# Encodeurs_Schematic.net
KiCad netlist of a schematic drawn in Altium Designer
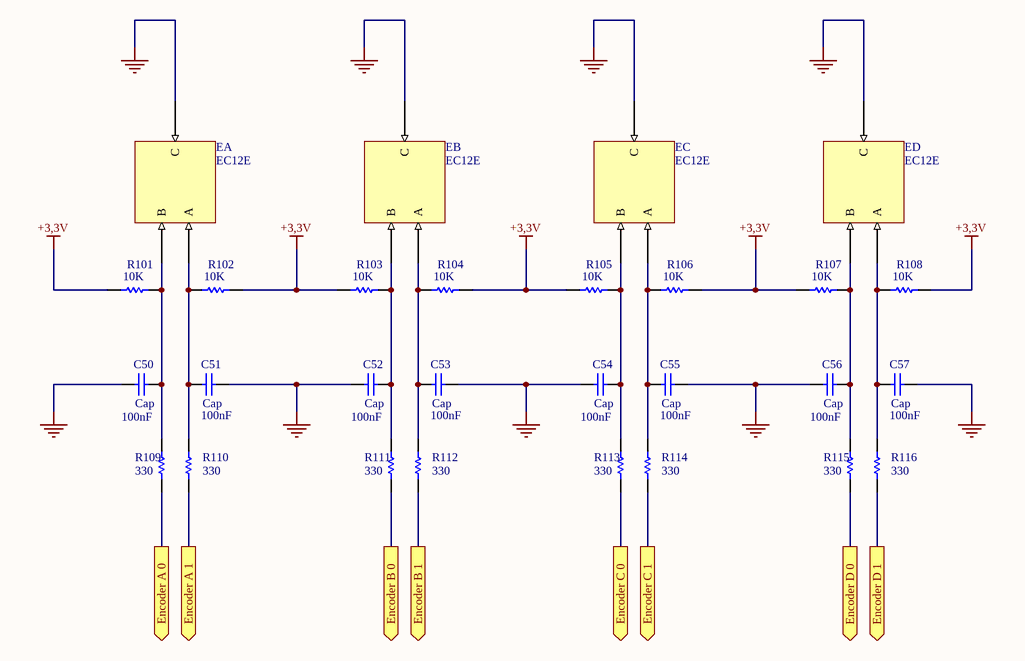
[diagram p0: Encodeurs.Schematic.SchDoc]

(export (version "E")
  (design (tool "Eeschema 10.0.6"))
  (components
    (comp (ref "C50")
      (value "Cap")
      (footprint "CAPC1608N - cap")
      (description "Capacitor")
      (fields (field (name "ALTIUM_VALUE") "100nF") (field (name "PUBLISHER") "Altium Limited"))
      (libsource (lib "Miscellaneous Devices") (part "Cap"))
    )
    (comp (ref "C51")
      (value "Cap")
      (footprint "CAPC1608N - cap")
      (description "Capacitor")
      (fields (field (name "ALTIUM_VALUE") "100nF") (field (name "PUBLISHER") "Altium Limited"))
      (libsource (lib "Miscellaneous Devices") (part "Cap"))
    )
    (comp (ref "C52")
      (value "Cap")
      (footprint "CAPC1608N - cap")
      (description "Capacitor")
      (fields (field (name "ALTIUM_VALUE") "100nF") (field (name "PUBLISHER") "Altium Limited"))
      (libsource (lib "Miscellaneous Devices") (part "Cap"))
    )
    (comp (ref "C53")
      (value "Cap")
      (footprint "CAPC1608N - cap")
      (description "Capacitor")
      (fields (field (name "ALTIUM_VALUE") "100nF") (field (name "PUBLISHER") "Altium Limited"))
      (libsource (lib "Miscellaneous Devices") (part "Cap"))
    )
    (comp (ref "C54")
      (value "Cap")
      (footprint "CAPC1608N - cap")
      (description "Capacitor")
      (fields (field (name "ALTIUM_VALUE") "100nF") (field (name "PUBLISHER") "Altium Limited"))
      (libsource (lib "Miscellaneous Devices") (part "Cap"))
    )
    (comp (ref "C55")
      (value "Cap")
      (footprint "CAPC1608N - cap")
      (description "Capacitor")
      (fields (field (name "ALTIUM_VALUE") "100nF") (field (name "PUBLISHER") "Altium Limited"))
      (libsource (lib "Miscellaneous Devices") (part "Cap"))
    )
    (comp (ref "C56")
      (value "Cap")
      (footprint "CAPC1608N - cap")
      (description "Capacitor")
      (fields (field (name "ALTIUM_VALUE") "100nF") (field (name "PUBLISHER") "Altium Limited"))
      (libsource (lib "Miscellaneous Devices") (part "Cap"))
    )
    (comp (ref "C57")
      (value "Cap")
      (footprint "CAPC1608N - cap")
      (description "Capacitor")
      (fields (field (name "ALTIUM_VALUE") "100nF") (field (name "PUBLISHER") "Altium Limited"))
      (libsource (lib "Miscellaneous Devices") (part "Cap"))
    )
    (comp (ref "EA")
      (value "EC12E")
      (footprint "EC12E")
      (libsource (lib "SynthyTwo.Components") (part "EC12E"))
    )
    (comp (ref "EB")
      (value "EC12E")
      (footprint "EC12E")
      (libsource (lib "SynthyTwo.Components") (part "EC12E"))
    )
    (comp (ref "EC")
      (value "EC12E")
      (footprint "EC12E")
      (libsource (lib "SynthyTwo.Components") (part "EC12E"))
    )
    (comp (ref "ED")
      (value "EC12E")
      (footprint "EC12E")
      (libsource (lib "SynthyTwo.Components") (part "EC12E"))
    )
    (comp (ref "R101")
      (value "10K")
      (footprint "CAPC1608N")
      (description "Resistor")
      (fields (field (name "PUBLISHER") "Altium Limited"))
      (libsource (lib "Miscellaneous Devices") (part "Res1"))
    )
    (comp (ref "R102")
      (value "10K")
      (footprint "CAPC1608N")
      (description "Resistor")
      (fields (field (name "PUBLISHER") "Altium Limited"))
      (libsource (lib "Miscellaneous Devices") (part "Res1"))
    )
    (comp (ref "R103")
      (value "10K")
      (footprint "CAPC1608N")
      (description "Resistor")
      (fields (field (name "PUBLISHER") "Altium Limited"))
      (libsource (lib "Miscellaneous Devices") (part "Res1"))
    )
    (comp (ref "R104")
      (value "10K")
      (footprint "CAPC1608N")
      (description "Resistor")
      (fields (field (name "PUBLISHER") "Altium Limited"))
      (libsource (lib "Miscellaneous Devices") (part "Res1"))
    )
    (comp (ref "R105")
      (value "10K")
      (footprint "CAPC1608N")
      (description "Resistor")
      (fields (field (name "PUBLISHER") "Altium Limited"))
      (libsource (lib "Miscellaneous Devices") (part "Res1"))
    )
    (comp (ref "R106")
      (value "10K")
      (footprint "CAPC1608N")
      (description "Resistor")
      (fields (field (name "PUBLISHER") "Altium Limited"))
      (libsource (lib "Miscellaneous Devices") (part "Res1"))
    )
    (comp (ref "R107")
      (value "10K")
      (footprint "CAPC1608N")
      (description "Resistor")
      (fields (field (name "PUBLISHER") "Altium Limited"))
      (libsource (lib "Miscellaneous Devices") (part "Res1"))
    )
    (comp (ref "R108")
      (value "10K")
      (footprint "CAPC1608N")
      (description "Resistor")
      (fields (field (name "PUBLISHER") "Altium Limited"))
      (libsource (lib "Miscellaneous Devices") (part "Res1"))
    )
    (comp (ref "R109")
      (value "330")
      (footprint "CAPC1608N")
      (description "Resistor")
      (fields (field (name "PUBLISHER") "Altium Limited"))
      (libsource (lib "Miscellaneous Devices") (part "Res1"))
    )
    (comp (ref "R110")
      (value "330")
      (footprint "CAPC1608N")
      (description "Resistor")
      (fields (field (name "PUBLISHER") "Altium Limited"))
      (libsource (lib "Miscellaneous Devices") (part "Res1"))
    )
    (comp (ref "R111")
      (value "330")
      (footprint "CAPC1608N")
      (description "Resistor")
      (fields (field (name "PUBLISHER") "Altium Limited"))
      (libsource (lib "Miscellaneous Devices") (part "Res1"))
    )
    (comp (ref "R112")
      (value "330")
      (footprint "CAPC1608N")
      (description "Resistor")
      (fields (field (name "PUBLISHER") "Altium Limited"))
      (libsource (lib "Miscellaneous Devices") (part "Res1"))
    )
    (comp (ref "R113")
      (value "330")
      (footprint "CAPC1608N")
      (description "Resistor")
      (fields (field (name "PUBLISHER") "Altium Limited"))
      (libsource (lib "Miscellaneous Devices") (part "Res1"))
    )
    (comp (ref "R114")
      (value "330")
      (footprint "CAPC1608N")
      (description "Resistor")
      (fields (field (name "PUBLISHER") "Altium Limited"))
      (libsource (lib "Miscellaneous Devices") (part "Res1"))
    )
    (comp (ref "R115")
      (value "330")
      (footprint "CAPC1608N")
      (description "Resistor")
      (fields (field (name "PUBLISHER") "Altium Limited"))
      (libsource (lib "Miscellaneous Devices") (part "Res1"))
    )
    (comp (ref "R116")
      (value "330")
      (footprint "CAPC1608N")
      (description "Resistor")
      (fields (field (name "PUBLISHER") "Altium Limited"))
      (libsource (lib "Miscellaneous Devices") (part "Res1"))
    )
  )
  (nets
    (net (code "1") (name "+3,3V") (class "Default")
      (node (ref "R101") (pin "1") (pinfunction "1_1") (pintype "passive"))
      (node (ref "R102") (pin "2") (pinfunction "2_2") (pintype "passive"))
      (node (ref "R103") (pin "1") (pinfunction "1_1") (pintype "passive"))
      (node (ref "R104") (pin "2") (pinfunction "2_2") (pintype "passive"))
      (node (ref "R105") (pin "1") (pinfunction "1_1") (pintype "passive"))
      (node (ref "R106") (pin "2") (pinfunction "2_2") (pintype "passive"))
      (node (ref "R107") (pin "1") (pinfunction "1_1") (pintype "passive"))
      (node (ref "R108") (pin "2") (pinfunction "2_2") (pintype "passive"))
    )
    (net (code "2") (name "/Encoder A 0") (class "Default")
      (node (ref "R109") (pin "1") (pinfunction "1_1") (pintype "passive"))
    )
    (net (code "3") (name "/Encoder A 1") (class "Default")
      (node (ref "R110") (pin "1") (pinfunction "1_1") (pintype "passive"))
    )
    (net (code "4") (name "/Encoder B 0") (class "Default")
      (node (ref "R111") (pin "1") (pinfunction "1_1") (pintype "passive"))
    )
    (net (code "5") (name "/Encoder B 1") (class "Default")
      (node (ref "R112") (pin "1") (pinfunction "1_1") (pintype "passive"))
    )
    (net (code "6") (name "/Encoder C 0") (class "Default")
      (node (ref "R113") (pin "1") (pinfunction "1_1") (pintype "passive"))
    )
    (net (code "7") (name "/Encoder C 1") (class "Default")
      (node (ref "R114") (pin "1") (pinfunction "1_1") (pintype "passive"))
    )
    (net (code "8") (name "/Encoder D 0") (class "Default")
      (node (ref "R115") (pin "1") (pinfunction "1_1") (pintype "passive"))
    )
    (net (code "9") (name "/Encoder D 1") (class "Default")
      (node (ref "R116") (pin "1") (pinfunction "1_1") (pintype "passive"))
    )
    (net (code "10") (name "GND") (class "Default")
      (node (ref "C50") (pin "1") (pinfunction "1_1") (pintype "passive"))
      (node (ref "C51") (pin "1") (pinfunction "1_1") (pintype "passive"))
      (node (ref "C52") (pin "1") (pinfunction "1_1") (pintype "passive"))
      (node (ref "C53") (pin "1") (pinfunction "1_1") (pintype "passive"))
      (node (ref "C54") (pin "1") (pinfunction "1_1") (pintype "passive"))
      (node (ref "C55") (pin "1") (pinfunction "1_1") (pintype "passive"))
      (node (ref "C56") (pin "1") (pinfunction "1_1") (pintype "passive"))
      (node (ref "C57") (pin "1") (pinfunction "1_1") (pintype "passive"))
      (node (ref "EA") (pin "3") (pinfunction "C_3") (pintype "input"))
      (node (ref "EB") (pin "3") (pinfunction "C_3") (pintype "input"))
      (node (ref "EC") (pin "3") (pinfunction "C_3") (pintype "input"))
      (node (ref "ED") (pin "3") (pinfunction "C_3") (pintype "input"))
    )
    (net (code "11") (name "Net-(EA-A)") (class "Default")
      (node (ref "C51") (pin "2") (pinfunction "2_2") (pintype "passive"))
      (node (ref "EA") (pin "1") (pinfunction "A_1") (pintype "input"))
      (node (ref "R102") (pin "1") (pinfunction "1_1") (pintype "passive"))
      (node (ref "R110") (pin "2") (pinfunction "2_2") (pintype "passive"))
    )
    (net (code "12") (name "Net-(EA-B)") (class "Default")
      (node (ref "C50") (pin "2") (pinfunction "2_2") (pintype "passive"))
      (node (ref "EA") (pin "2") (pinfunction "B_2") (pintype "input"))
      (node (ref "R101") (pin "2") (pinfunction "2_2") (pintype "passive"))
      (node (ref "R109") (pin "2") (pinfunction "2_2") (pintype "passive"))
    )
    (net (code "13") (name "Net-(EB-A)") (class "Default")
      (node (ref "C53") (pin "2") (pinfunction "2_2") (pintype "passive"))
      (node (ref "EB") (pin "1") (pinfunction "A_1") (pintype "input"))
      (node (ref "R104") (pin "1") (pinfunction "1_1") (pintype "passive"))
      (node (ref "R112") (pin "2") (pinfunction "2_2") (pintype "passive"))
    )
    (net (code "14") (name "Net-(EB-B)") (class "Default")
      (node (ref "C52") (pin "2") (pinfunction "2_2") (pintype "passive"))
      (node (ref "EB") (pin "2") (pinfunction "B_2") (pintype "input"))
      (node (ref "R103") (pin "2") (pinfunction "2_2") (pintype "passive"))
      (node (ref "R111") (pin "2") (pinfunction "2_2") (pintype "passive"))
    )
    (net (code "15") (name "Net-(EC-A)") (class "Default")
      (node (ref "C55") (pin "2") (pinfunction "2_2") (pintype "passive"))
      (node (ref "EC") (pin "1") (pinfunction "A_1") (pintype "input"))
      (node (ref "R106") (pin "1") (pinfunction "1_1") (pintype "passive"))
      (node (ref "R114") (pin "2") (pinfunction "2_2") (pintype "passive"))
    )
    (net (code "16") (name "Net-(EC-B)") (class "Default")
      (node (ref "C54") (pin "2") (pinfunction "2_2") (pintype "passive"))
      (node (ref "EC") (pin "2") (pinfunction "B_2") (pintype "input"))
      (node (ref "R105") (pin "2") (pinfunction "2_2") (pintype "passive"))
      (node (ref "R113") (pin "2") (pinfunction "2_2") (pintype "passive"))
    )
    (net (code "17") (name "Net-(ED-A)") (class "Default")
      (node (ref "C57") (pin "2") (pinfunction "2_2") (pintype "passive"))
      (node (ref "ED") (pin "1") (pinfunction "A_1") (pintype "input"))
      (node (ref "R108") (pin "1") (pinfunction "1_1") (pintype "passive"))
      (node (ref "R116") (pin "2") (pinfunction "2_2") (pintype "passive"))
    )
    (net (code "18") (name "Net-(ED-B)") (class "Default")
      (node (ref "C56") (pin "2") (pinfunction "2_2") (pintype "passive"))
      (node (ref "ED") (pin "2") (pinfunction "B_2") (pintype "input"))
      (node (ref "R107") (pin "2") (pinfunction "2_2") (pintype "passive"))
      (node (ref "R115") (pin "2") (pinfunction "2_2") (pintype "passive"))
    )
  )
)
